# ESP32_S3.net
KiCad netlist of a schematic drawn in Altium Designer
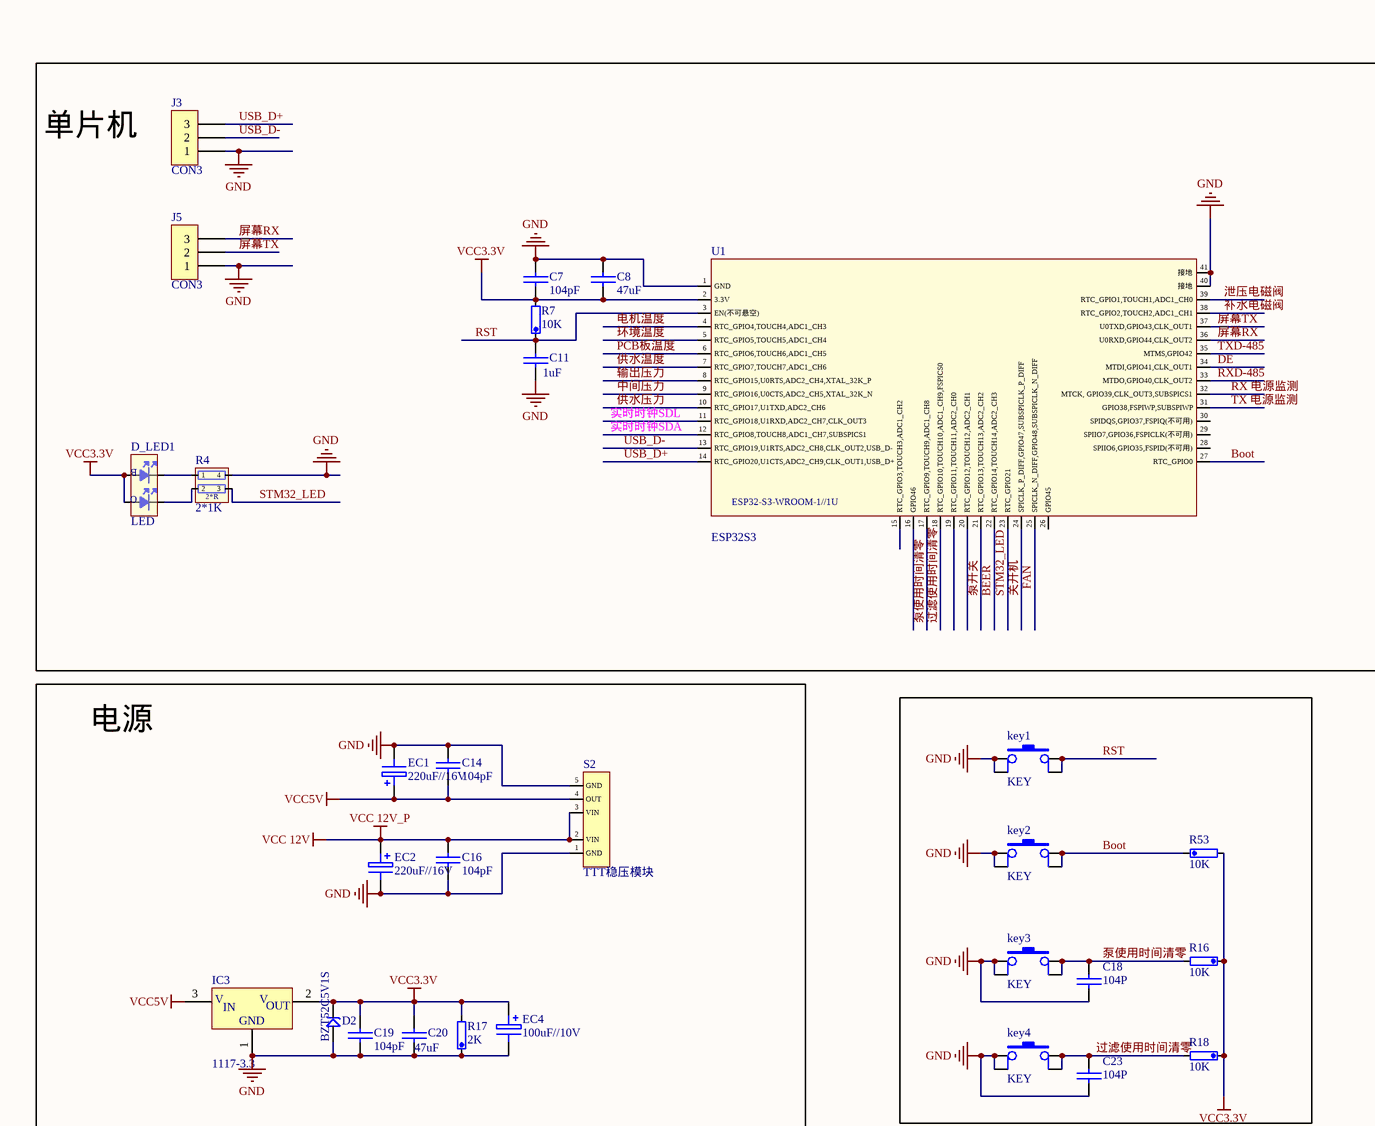
[diagram p0: 喷雾系统ESP32 S3.SchDoc, top left]
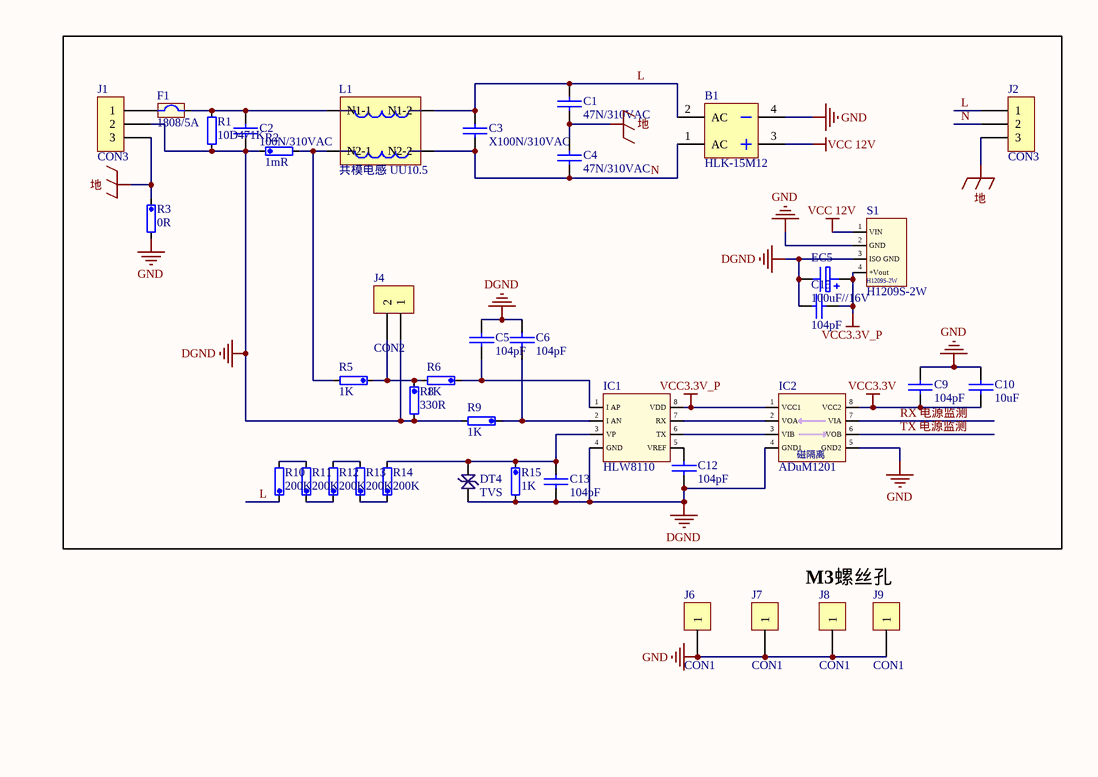
[diagram p1: 喷雾系统ESP32 S3.SchDoc, top right]
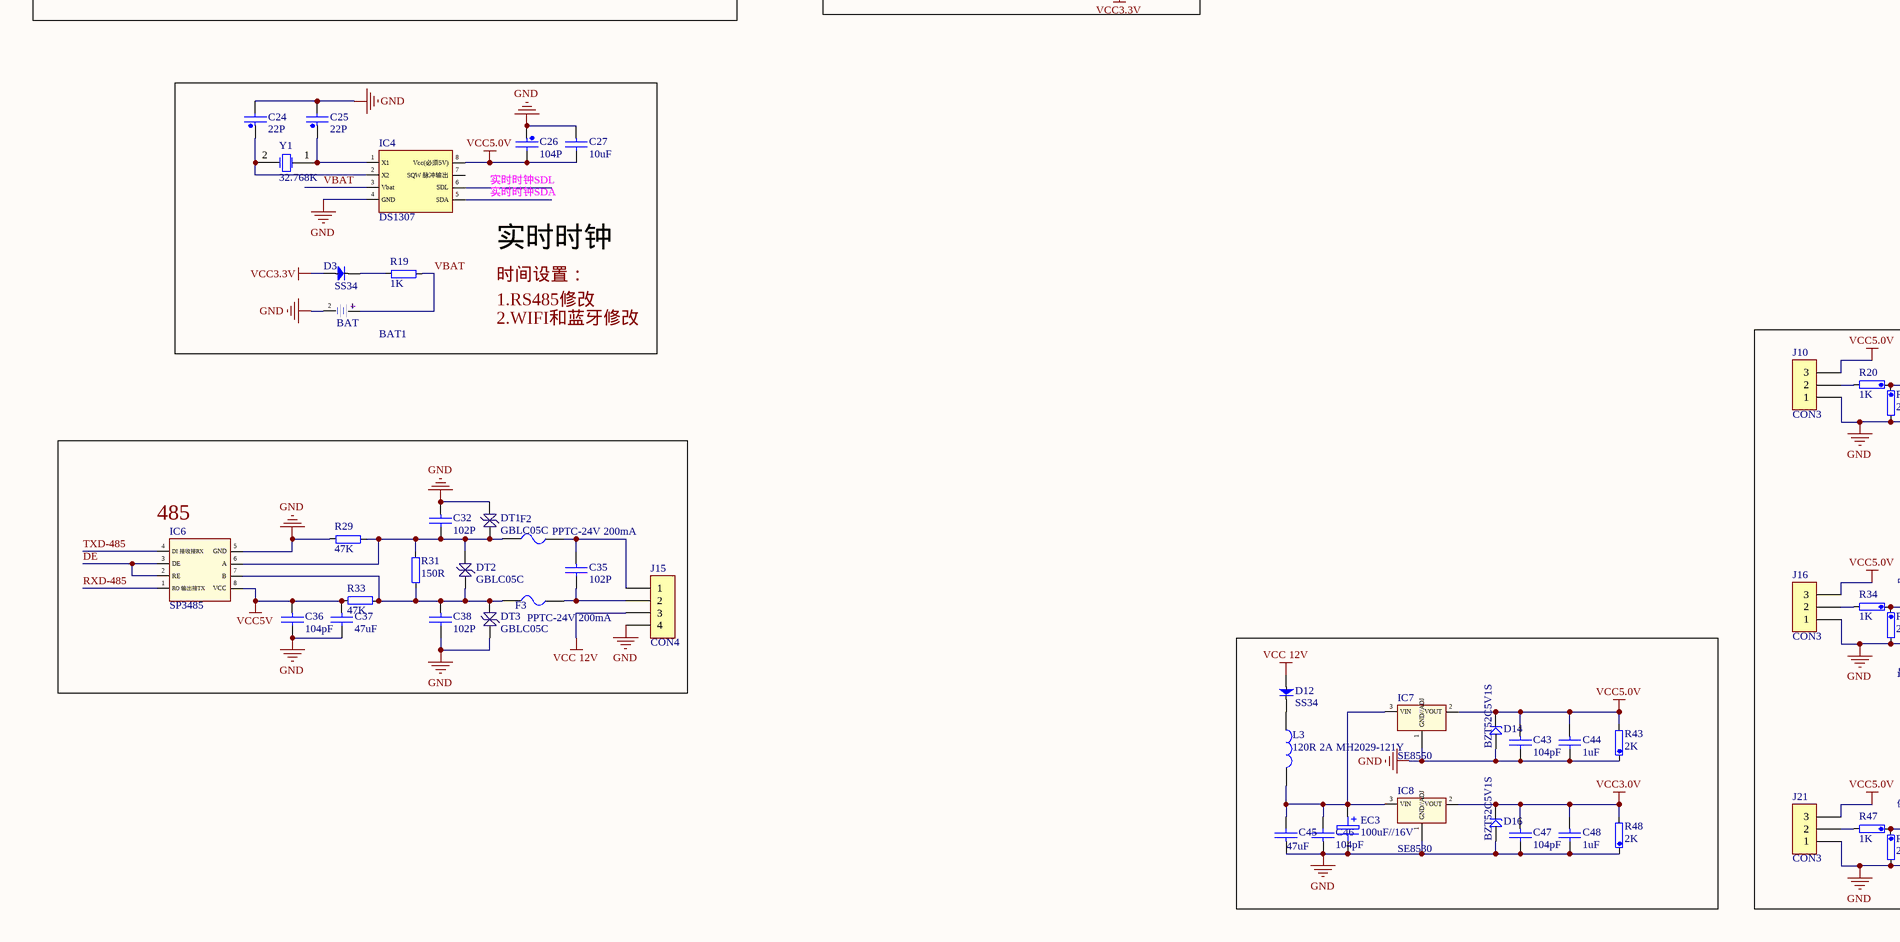
[diagram p2: 喷雾系统ESP32 S3.SchDoc, bottom left]
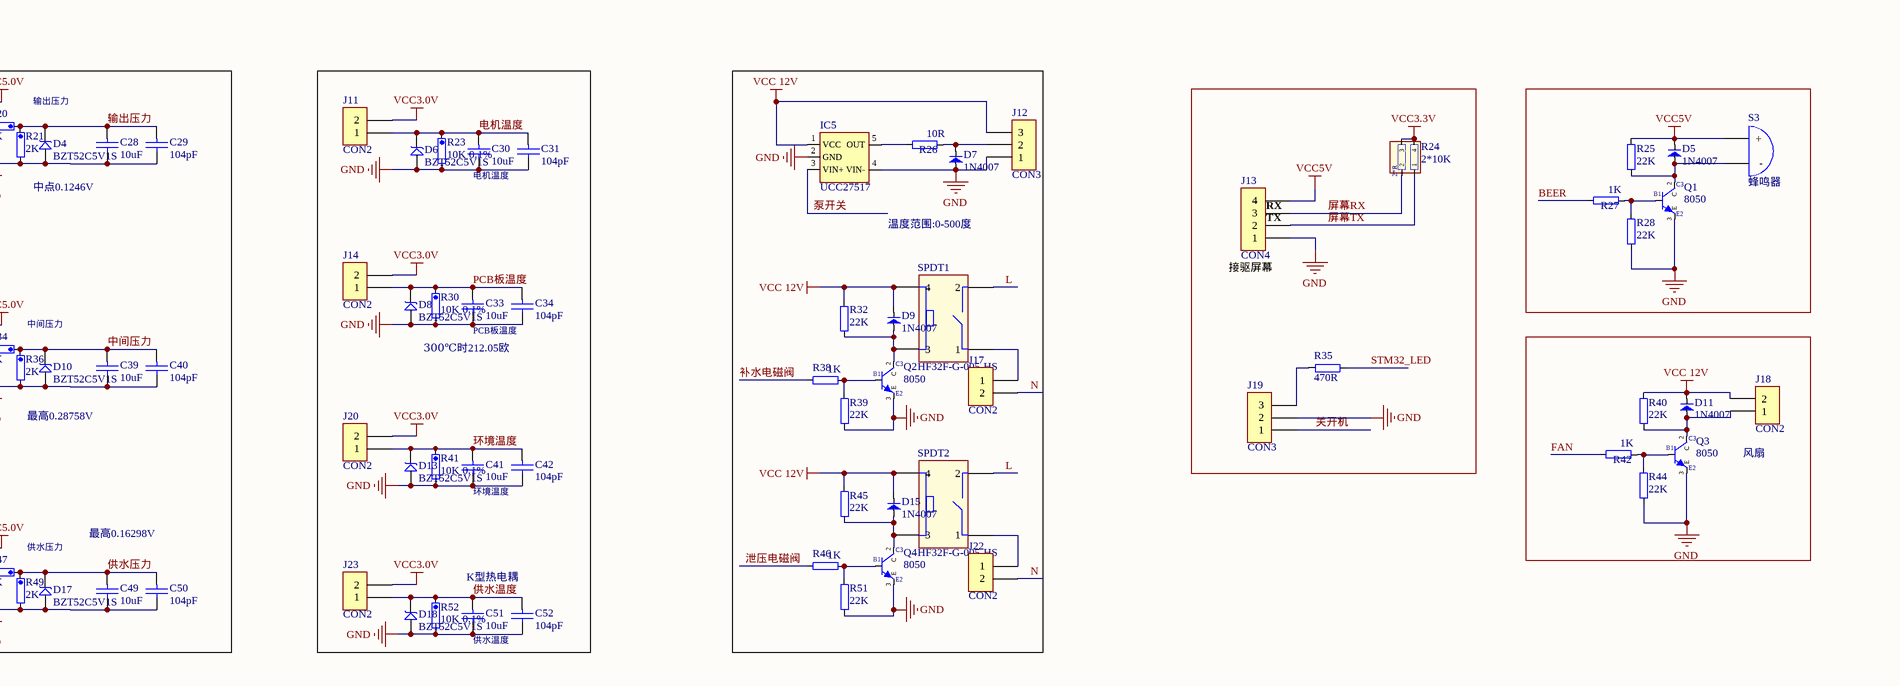
[diagram p3: 喷雾系统ESP32 S3.SchDoc, bottom right]

(export (version "E")
  (design (tool "Eeschema 10.0.6"))
  (components
    (comp (ref "B1")
      (value "HLK-15M12")
      (footprint "电源模块15W AC转DC HI-link")
      (description "HI-link")
      (libsource (lib "西洲电子元件库") (part "AC-DC模块"))
    )
    (comp (ref "BAT1")
      (value "BAT")
      (footprint "直插锂电池")
      (description "电池")
      (libsource (lib "西洲电子元件库") (part "电池 BAT"))
    )
    (comp (ref "C1") (value "47N/310VAC") (footprint "安规Y电容") (libsource (lib "功放DIY") (part "CAP")))
    (comp (ref "C2") (value "100N/310VAC") (footprint "安规X电容") (libsource (lib "功放DIY") (part "CAP")))
    (comp (ref "C3")
      (value "X100N/310VAC")
      (footprint "安规X电容")
      (description "安规电容")
      (libsource (lib "西洲电子元件库") (part "CAP"))
    )
    (comp (ref "C4") (value "47N/310VAC") (footprint "安规Y电容") (libsource (lib "功放DIY") (part "CAP")))
    (comp (ref "C5")
      (value "104pF")
      (footprint "B0805")
      (description "电容")
      (libsource (lib "西洲电子元件库") (part "CAP"))
    )
    (comp (ref "C6")
      (value "104pF")
      (footprint "B0805")
      (description "电容")
      (libsource (lib "西洲电子元件库") (part "CAP"))
    )
    (comp (ref "C7")
      (value "104pF")
      (footprint "B0805")
      (description "电容")
      (libsource (lib "西洲电子元件库") (part "CAP"))
    )
    (comp (ref "C8")
      (value "47uF")
      (footprint "B0805")
      (description "电容")
      (libsource (lib "西洲电子元件库") (part "CAP"))
    )
    (comp (ref "C9")
      (value "104pF")
      (footprint "B0805")
      (description "电容")
      (libsource (lib "西洲电子元件库") (part "CAP"))
    )
    (comp (ref "C10")
      (value "10uF")
      (footprint "B0805")
      (description "电容")
      (libsource (lib "西洲电子元件库") (part "CAP"))
    )
    (comp (ref "C11")
      (value "1uF")
      (footprint "B0805")
      (description "电容")
      (libsource (lib "西洲电子元件库") (part "CAP"))
    )
    (comp (ref "C12")
      (value "104pF")
      (footprint "B0805")
      (description "电容")
      (libsource (lib "西洲电子元件库") (part "CAP"))
    )
    (comp (ref "C13")
      (value "104pF")
      (footprint "B0805")
      (description "电容")
      (libsource (lib "西洲电子元件库") (part "CAP"))
    )
    (comp (ref "C14") (value "104pF") (footprint "B0805") (libsource (lib "功放DIY") (part "CAP")))
    (comp (ref "C15")
      (value "104pF")
      (footprint "B0805")
      (description "电容")
      (libsource (lib "西洲电子元件库") (part "CAP"))
    )
    (comp (ref "C16") (value "104pF") (footprint "B0805") (libsource (lib "功放DIY") (part "CAP")))
    (comp (ref "C18") (value "104P") (footprint "B0805") (libsource (lib "功放DIY") (part "CAP")))
    (comp (ref "C19")
      (value "104pF")
      (footprint "B0805")
      (description "电容")
      (libsource (lib "西洲电子元件库") (part "CAP"))
    )
    (comp (ref "C20")
      (value "47uF")
      (footprint "B0805")
      (description "电容")
      (libsource (lib "西洲电子元件库") (part "CAP"))
    )
    (comp (ref "C23") (value "104P") (footprint "B0805") (libsource (lib "功放DIY") (part "CAP")))
    (comp (ref "C24") (value "22P") (footprint "B0603") (libsource (lib "") (part "CAP_1")))
    (comp (ref "C25") (value "22P") (footprint "B0603") (libsource (lib "") (part "CAP_1")))
    (comp (ref "C26") (value "104P") (footprint "B0805") (libsource (lib "") (part "CAP_1")))
    (comp (ref "C27") (value "10uF") (footprint "B0805") (libsource (lib "功放DIY") (part "CAP")))
    (comp (ref "C28")
      (value "10uF")
      (footprint "B0805")
      (description "电容")
      (libsource (lib "西洲电子元件库") (part "CAP"))
    )
    (comp (ref "C29")
      (value "104pF")
      (footprint "B0805")
      (description "电容")
      (libsource (lib "西洲电子元件库") (part "CAP"))
    )
    (comp (ref "C30")
      (value "10uF")
      (footprint "B0805")
      (description "电容")
      (libsource (lib "西洲电子元件库") (part "CAP"))
    )
    (comp (ref "C31")
      (value "104pF")
      (footprint "B0805")
      (description "电容")
      (libsource (lib "西洲电子元件库") (part "CAP"))
    )
    (comp (ref "C32") (value "102P") (footprint "B0805") (libsource (lib "功放DIY") (part "CAP")))
    (comp (ref "C33")
      (value "10uF")
      (footprint "B0805")
      (description "电容")
      (libsource (lib "西洲电子元件库") (part "CAP"))
    )
    (comp (ref "C34")
      (value "104pF")
      (footprint "B0805")
      (description "电容")
      (libsource (lib "西洲电子元件库") (part "CAP"))
    )
    (comp (ref "C35") (value "102P") (footprint "B0805") (libsource (lib "功放DIY") (part "CAP")))
    (comp (ref "C36")
      (value "104pF")
      (footprint "B0805")
      (description "电容")
      (libsource (lib "西洲电子元件库") (part "CAP"))
    )
    (comp (ref "C37")
      (value "47uF")
      (footprint "B0805")
      (description "电容")
      (libsource (lib "西洲电子元件库") (part "CAP"))
    )
    (comp (ref "C38") (value "102P") (footprint "B0805") (libsource (lib "功放DIY") (part "CAP")))
    (comp (ref "C39")
      (value "10uF")
      (footprint "B0805")
      (description "电容")
      (libsource (lib "西洲电子元件库") (part "CAP"))
    )
    (comp (ref "C40")
      (value "104pF")
      (footprint "B0805")
      (description "电容")
      (libsource (lib "西洲电子元件库") (part "CAP"))
    )
    (comp (ref "C41")
      (value "10uF")
      (footprint "B0805")
      (description "电容")
      (libsource (lib "西洲电子元件库") (part "CAP"))
    )
    (comp (ref "C42")
      (value "104pF")
      (footprint "B0805")
      (description "电容")
      (libsource (lib "西洲电子元件库") (part "CAP"))
    )
    (comp (ref "C43")
      (value "104pF")
      (footprint "B0805")
      (description "电容")
      (libsource (lib "西洲电子元件库") (part "CAP"))
    )
    (comp (ref "C44")
      (value "1uF")
      (footprint "B0805")
      (description "电容")
      (libsource (lib "西洲电子元件库") (part "CAP"))
    )
    (comp (ref "C45")
      (value "47uF")
      (footprint "B0805")
      (description "电容")
      (libsource (lib "西洲电子元件库") (part "CAP"))
    )
    (comp (ref "C46")
      (value "104pF")
      (footprint "B0805")
      (description "电容")
      (libsource (lib "西洲电子元件库") (part "CAP"))
    )
    (comp (ref "C47")
      (value "104pF")
      (footprint "B0805")
      (description "电容")
      (libsource (lib "西洲电子元件库") (part "CAP"))
    )
    (comp (ref "C48")
      (value "1uF")
      (footprint "B0805")
      (description "电容")
      (libsource (lib "西洲电子元件库") (part "CAP"))
    )
    (comp (ref "C49")
      (value "10uF")
      (footprint "B0805")
      (description "电容")
      (libsource (lib "西洲电子元件库") (part "CAP"))
    )
    (comp (ref "C50")
      (value "104pF")
      (footprint "B0805")
      (description "电容")
      (libsource (lib "西洲电子元件库") (part "CAP"))
    )
    (comp (ref "C51")
      (value "10uF")
      (footprint "B0805")
      (description "电容")
      (libsource (lib "西洲电子元件库") (part "CAP"))
    )
    (comp (ref "C52")
      (value "104pF")
      (footprint "B0805")
      (description "电容")
      (libsource (lib "西洲电子元件库") (part "CAP"))
    )
    (comp (ref "D2") (value "BZT52C5V1S") (footprint "SOD-323") (libsource (lib "西洲电子元件库") (part "单向稳压二极管")))
    (comp (ref "D3") (value "SS34") (footprint "SOD-323") (libsource (lib "") (part "DIODE_1")))
    (comp (ref "D4") (value "BZT52C5V1S") (footprint "SOD-323") (libsource (lib "西洲电子元件库") (part "单向稳压二极管")))
    (comp (ref "D5") (value "1N4007") (footprint "SOD-323") (libsource (lib "西洲电子元件库") (part "DIODE")))
    (comp (ref "D6") (value "BZT52C5V1S") (footprint "SOD-323") (libsource (lib "西洲电子元件库") (part "单向稳压二极管")))
    (comp (ref "D7") (value "1N4007") (footprint "SOD-323") (libsource (lib "西洲电子元件库") (part "DIODE")))
    (comp (ref "D8") (value "BZT52C5V1S") (footprint "SOD-323") (libsource (lib "西洲电子元件库") (part "单向稳压二极管")))
    (comp (ref "D9") (value "1N4007") (footprint "SOD-323") (libsource (lib "西洲电子元件库") (part "DIODE")))
    (comp (ref "D10") (value "BZT52C5V1S") (footprint "SOD-323") (libsource (lib "西洲电子元件库") (part "单向稳压二极管")))
    (comp (ref "D11") (value "1N4007") (footprint "SOD-323") (libsource (lib "西洲电子元件库") (part "DIODE")))
    (comp (ref "D12") (value "SS34") (footprint "SOD-323") (libsource (lib "") (part "DIODE_1")))
    (comp (ref "D13") (value "BZT52C5V1S") (footprint "SOD-323") (libsource (lib "西洲电子元件库") (part "单向稳压二极管")))
    (comp (ref "D14") (value "BZT52C5V1S") (footprint "SOD-323") (libsource (lib "西洲电子元件库") (part "单向稳压二极管")))
    (comp (ref "D15") (value "1N4007") (footprint "SOD-323") (libsource (lib "西洲电子元件库") (part "DIODE")))
    (comp (ref "D16") (value "BZT52C5V1S") (footprint "SOD-323") (libsource (lib "西洲电子元件库") (part "单向稳压二极管")))
    (comp (ref "D17") (value "BZT52C5V1S") (footprint "SOD-323") (libsource (lib "西洲电子元件库") (part "单向稳压二极管")))
    (comp (ref "D18") (value "BZT52C5V1S") (footprint "SOD-323") (libsource (lib "西洲电子元件库") (part "单向稳压二极管")))
    (comp (ref "DT1") (value "GBLC05C") (footprint "SOD-323-12") (libsource (lib "西洲电子元件库") (part "TVS")))
    (comp (ref "DT2") (value "GBLC05C") (footprint "SOD-323-12") (libsource (lib "西洲电子元件库") (part "TVS")))
    (comp (ref "DT3") (value "GBLC05C") (footprint "SOD-323-12") (libsource (lib "西洲电子元件库") (part "TVS")))
    (comp (ref "DT4") (value "TVS") (footprint "SOD-323") (libsource (lib "") (part "TVS_1")))
    (comp (ref "D_LED1")
      (value "LED")
      (footprint "双色LED 1615")
      (description "双色LED 橙蓝")
      (libsource (lib "西洲电子元件库") (part "双色LED 橙蓝"))
    )
    (comp (ref "EC1") (value "220uF//16V") (footprint "贴片电容6.3*5.4") (libsource (lib "功放DIY") (part "EC")))
    (comp (ref "EC2") (value "220uF//16V") (footprint "贴片电容6.3*5.4") (libsource (lib "功放DIY") (part "EC")))
    (comp (ref "EC3") (value "100uF//16V") (footprint "C型 电容") (libsource (lib "功放DIY") (part "EC")))
    (comp (ref "EC4") (value "100uF//10V") (footprint "C型 电容") (libsource (lib "功放DIY") (part "EC")))
    (comp (ref "EC5") (value "100uF//16V") (footprint "C型 电容") (libsource (lib "功放DIY") (part "EC")))
    (comp (ref "F1") (value "1808/5A") (footprint "1808贴片保险") (libsource (lib "功放DIY") (part "保险")))
    (comp (ref "F2")
      (value "PPTC-24V 200mA")
      (footprint "FU 0805")
      (description "贴片保险丝")
      (fields (field (name "版权归属") "源创客"))
      (libsource (lib "保险丝-晶振") (part "FU"))
    )
    (comp (ref "F3")
      (value "PPTC-24V 200mA")
      (footprint "FU 0805")
      (description "贴片保险丝")
      (fields (field (name "版权归属") "源创客"))
      (libsource (lib "保险丝-晶振") (part "FU"))
    )
    (comp (ref "IC1")
      (value "HLW8110")
      (footprint "SOP8")
      (description "电能计量")
      (libsource (lib "西洲电子元件库") (part "HLW8110"))
    )
    (comp (ref "IC2")
      (value "ADuM1201")
      (footprint "SOP8")
      (description "磁隔离 ADuM1201")
      (libsource (lib "西洲电子元件库") (part "磁隔离"))
    )
    (comp (ref "IC3") (value "1117-3.3") (footprint "SOT-223") (libsource (lib "西洲电子元件库") (part "1117")))
    (comp (ref "IC4") (value "DS1307") (footprint "SOP8") (libsource (lib "西洲电子元件库") (part "DS1307")))
    (comp (ref "IC5")
      (value "UCC27517")
      (footprint "SOT23-5")
      (description "场管驱动")
      (libsource (lib "西洲电子元件库") (part "场管驱动 UCC27517"))
    )
    (comp (ref "IC6")
      (value "SP3485")
      (footprint "SOP8")
      (description "RS485 收发")
      (libsource (lib "西洲电子元件库") (part "SP3485"))
    )
    (comp (ref "IC7")
      (value "SE8550")
      (footprint "SOT_89")
      (description "稳压LOD+")
      (libsource (lib "西洲电子元件库") (part "稳压LOD+ 2脚输出"))
    )
    (comp (ref "IC8")
      (value "SE8530")
      (footprint "SOT23_231")
      (description "稳压LOD+")
      (libsource (lib "西洲电子元件库") (part "稳压LOD+ 2脚输出"))
    )
    (comp (ref "J1")
      (value "CON3")
      (footprint "CON3_5.08 弯")
      (description "Connector")
      (libsource (lib "") (part "CON3_2"))
    )
    (comp (ref "J2")
      (value "CON3")
      (footprint "CON3_5.08 弯")
      (description "Connector")
      (libsource (lib "") (part "CON3_3"))
    )
    (comp (ref "J3")
      (value "CON3")
      (footprint "SIP3_2.0")
      (description "Connector")
      (libsource (lib "西洲电子元件库") (part "CON3"))
    )
    (comp (ref "J4")
      (value "CON2")
      (footprint "XH2.54-2P 弯")
      (description "Connector")
      (libsource (lib "") (part "CON2_1"))
    )
    (comp (ref "J5")
      (value "CON3")
      (footprint "SIP3_2.0")
      (description "Connector")
      (libsource (lib "西洲电子元件库") (part "CON3"))
    )
    (comp (ref "J6")
      (value "CON1")
      (footprint "螺丝孔")
      (description "Connector")
      (libsource (lib "功放DIY") (part "CON1"))
    )
    (comp (ref "J7")
      (value "CON1")
      (footprint "螺丝孔")
      (description "Connector")
      (libsource (lib "功放DIY") (part "CON1"))
    )
    (comp (ref "J8")
      (value "CON1")
      (footprint "螺丝孔")
      (description "Connector")
      (libsource (lib "功放DIY") (part "CON1"))
    )
    (comp (ref "J9")
      (value "CON1")
      (footprint "螺丝孔")
      (description "Connector")
      (libsource (lib "功放DIY") (part "CON1"))
    )
    (comp (ref "J10")
      (value "CON3")
      (footprint "XHB2.54-3")
      (description "Connector")
      (libsource (lib "西洲电子元件库") (part "CON3"))
    )
    (comp (ref "J11")
      (value "CON2")
      (footprint "PH2.0_2P_直针")
      (description "Connector")
      (libsource (lib "") (part "CON2_3"))
    )
    (comp (ref "J12")
      (value "CON3")
      (footprint "XHB2.54-3")
      (description "Connector")
      (libsource (lib "") (part "CON3_1"))
    )
    (comp (ref "J13")
      (value "CON4")
      (footprint "XHB2.54_4")
      (description "Connector")
      (libsource (lib "") (part "CON4_1"))
    )
    (comp (ref "J14")
      (value "CON2")
      (footprint "PH2.0_2P_直针")
      (description "Connector")
      (libsource (lib "") (part "CON2_3"))
    )
    (comp (ref "J15")
      (value "CON4")
      (footprint "XHB2.54_4")
      (description "Connector")
      (libsource (lib "西洲电子元件库") (part "CON4"))
    )
    (comp (ref "J16")
      (value "CON3")
      (footprint "XHB2.54-3")
      (description "Connector")
      (libsource (lib "西洲电子元件库") (part "CON3"))
    )
    (comp (ref "J17")
      (value "CON2")
      (footprint "CON2-5.08 弯")
      (description "Connector")
      (libsource (lib "") (part "CON2_2"))
    )
    (comp (ref "J18")
      (value "CON2")
      (footprint "XHB2.54-2")
      (description "Connector")
      (libsource (lib "西洲电子元件库") (part "CON2"))
    )
    (comp (ref "J19")
      (value "CON3")
      (footprint "PH2.0_3P_直针")
      (description "Connector")
      (libsource (lib "西洲电子元件库") (part "CON3"))
    )
    (comp (ref "J20")
      (value "CON2")
      (footprint "PH2.0_2P_直针")
      (description "Connector")
      (libsource (lib "") (part "CON2_3"))
    )
    (comp (ref "J21")
      (value "CON3")
      (footprint "XHB2.54-3")
      (description "Connector")
      (libsource (lib "西洲电子元件库") (part "CON3"))
    )
    (comp (ref "J22")
      (value "CON2")
      (footprint "CON2-5.08 弯")
      (description "Connector")
      (libsource (lib "") (part "CON2_2"))
    )
    (comp (ref "J23")
      (value "CON2")
      (footprint "PH2.0_2P_直针")
      (description "Connector")
      (libsource (lib "") (part "CON2_3"))
    )
    (comp (ref "key1") (value "KEY") (footprint "3*4*2.5按键") (libsource (lib "功放DIY") (part "KEY")))
    (comp (ref "key2") (value "KEY") (footprint "3*4*2.5按键") (libsource (lib "功放DIY") (part "KEY")))
    (comp (ref "key3") (value "KEY") (footprint "3*4*2.5按键") (libsource (lib "功放DIY") (part "KEY")))
    (comp (ref "key4") (value "KEY") (footprint "3*4*2.5按键") (libsource (lib "功放DIY") (part "KEY")))
    (comp (ref "L1")
      (value "共模电感 UU10.5")
      (footprint "UU10 共模电感")
      (libsource (lib "西洲电子元件库") (part "共模电感 UU10.5"))
    )
    (comp (ref "L3")
      (value "120R 2A MH2029-121Y")
      (footprint "B0805")
      (libsource (lib "西洲电子元件库") (part "INDUCTOR"))
    )
    (comp (ref "Q1")
      (value "8050")
      (footprint "SOT231")
      (description "NPN Transistor")
      (libsource (lib "西洲电子元件库") (part "NPN"))
    )
    (comp (ref "Q2")
      (value "8050")
      (footprint "SOT231")
      (description "NPN Transistor")
      (libsource (lib "西洲电子元件库") (part "NPN"))
    )
    (comp (ref "Q3")
      (value "8050")
      (footprint "SOT231")
      (description "NPN Transistor")
      (libsource (lib "西洲电子元件库") (part "NPN"))
    )
    (comp (ref "Q4")
      (value "8050")
      (footprint "SOT231")
      (description "NPN Transistor")
      (libsource (lib "西洲电子元件库") (part "NPN"))
    )
    (comp (ref "R1") (value "10D471K") (footprint "10D471K") (libsource (lib "功放DIY") (part "RES")))
    (comp (ref "R2") (value "1mR") (footprint "B2410") (libsource (lib "西洲电子元件库") (part "RES")))
    (comp (ref "R3") (value "0R") (footprint "B0805") (libsource (lib "西洲电子元件库") (part "RES")))
    (comp (ref "R4")
      (value "2*1K")
      (footprint "B0402-2")
      (description "排阻2P")
      (libsource (lib "西洲电子元件库") (part "排阻2P"))
    )
    (comp (ref "R5") (value "1K") (footprint "B0603") (libsource (lib "西洲电子元件库") (part "RES")))
    (comp (ref "R6") (value "1K") (footprint "B0603") (libsource (lib "西洲电子元件库") (part "RES")))
    (comp (ref "R7") (value "10K") (footprint "B0603") (libsource (lib "西洲电子元件库") (part "RES")))
    (comp (ref "R8") (value "330R") (footprint "B0805") (libsource (lib "西洲电子元件库") (part "RES")))
    (comp (ref "R9") (value "1K") (footprint "B0603") (libsource (lib "西洲电子元件库") (part "RES")))
    (comp (ref "R10") (value "200K") (footprint "B0603") (libsource (lib "西洲电子元件库") (part "RES")))
    (comp (ref "R11") (value "200K") (footprint "B0603") (libsource (lib "西洲电子元件库") (part "RES")))
    (comp (ref "R12") (value "200K") (footprint "B0603") (libsource (lib "西洲电子元件库") (part "RES")))
    (comp (ref "R13") (value "200K") (footprint "B0603") (libsource (lib "西洲电子元件库") (part "RES")))
    (comp (ref "R14") (value "200K") (footprint "B0603") (libsource (lib "西洲电子元件库") (part "RES")))
    (comp (ref "R15") (value "1K") (footprint "B0805") (libsource (lib "西洲电子元件库") (part "RES")))
    (comp (ref "R16") (value "10K") (footprint "B0603") (libsource (lib "西洲电子元件库") (part "RES")))
    (comp (ref "R17") (value "2K") (footprint "B0603") (libsource (lib "西洲电子元件库") (part "RES")))
    (comp (ref "R18") (value "10K") (footprint "B0603") (libsource (lib "西洲电子元件库") (part "RES")))
    (comp (ref "R19") (value "1K") (footprint "B0603") (libsource (lib "功放DIY") (part "RES")))
    (comp (ref "R20") (value "1K") (footprint "B0603") (libsource (lib "西洲电子元件库") (part "RES")))
    (comp (ref "R21") (value "2K") (footprint "B0603") (libsource (lib "西洲电子元件库") (part "RES")))
    (comp (ref "R23") (value "10K 0.1%") (footprint "B0603") (libsource (lib "西洲电子元件库") (part "RES")))
    (comp (ref "R24")
      (value "2*10K")
      (footprint "B0402-2")
      (description "排阻2P")
      (libsource (lib "西洲电子元件库") (part "排阻2P"))
    )
    (comp (ref "R25") (value "22K") (footprint "B0603") (libsource (lib "功放DIY") (part "RES")))
    (comp (ref "R26") (value "10R") (footprint "B0603") (libsource (lib "功放DIY") (part "RES")))
    (comp (ref "R27") (value "1K") (footprint "B0603") (libsource (lib "功放DIY") (part "RES")))
    (comp (ref "R28") (value "22K") (footprint "B0603") (libsource (lib "功放DIY") (part "RES")))
    (comp (ref "R29") (value "47K") (footprint "B0603") (libsource (lib "功放DIY") (part "RES")))
    (comp (ref "R30") (value "10K 0.1%") (footprint "B0603") (libsource (lib "西洲电子元件库") (part "RES")))
    (comp (ref "R31") (value "150R") (footprint "B0603") (libsource (lib "功放DIY") (part "RES")))
    (comp (ref "R32") (value "22K") (footprint "B0603") (libsource (lib "功放DIY") (part "RES")))
    (comp (ref "R33") (value "47K") (footprint "B0603") (libsource (lib "功放DIY") (part "RES")))
    (comp (ref "R34") (value "1K") (footprint "B0603") (libsource (lib "西洲电子元件库") (part "RES")))
    (comp (ref "R35") (value "470R") (footprint "B0603") (libsource (lib "功放DIY") (part "RES")))
    (comp (ref "R36") (value "2K") (footprint "B0603") (libsource (lib "西洲电子元件库") (part "RES")))
    (comp (ref "R38") (value "1K") (footprint "B0603") (libsource (lib "功放DIY") (part "RES")))
    (comp (ref "R39") (value "22K") (footprint "B0603") (libsource (lib "功放DIY") (part "RES")))
    (comp (ref "R40") (value "22K") (footprint "B0603") (libsource (lib "功放DIY") (part "RES")))
    (comp (ref "R41") (value "10K 0.1%") (footprint "B0603") (libsource (lib "西洲电子元件库") (part "RES")))
    (comp (ref "R42") (value "1K") (footprint "B0603") (libsource (lib "功放DIY") (part "RES")))
    (comp (ref "R43") (value "2K") (footprint "B0603") (libsource (lib "西洲电子元件库") (part "RES")))
    (comp (ref "R44") (value "22K") (footprint "B0603") (libsource (lib "功放DIY") (part "RES")))
    (comp (ref "R45") (value "22K") (footprint "B0603") (libsource (lib "功放DIY") (part "RES")))
    (comp (ref "R46") (value "1K") (footprint "B0603") (libsource (lib "功放DIY") (part "RES")))
    (comp (ref "R47") (value "1K") (footprint "B0603") (libsource (lib "西洲电子元件库") (part "RES")))
    (comp (ref "R48") (value "2K") (footprint "B0603") (libsource (lib "西洲电子元件库") (part "RES")))
    (comp (ref "R49") (value "2K") (footprint "B0603") (libsource (lib "西洲电子元件库") (part "RES")))
    (comp (ref "R51") (value "22K") (footprint "B0603") (libsource (lib "功放DIY") (part "RES")))
    (comp (ref "R52") (value "10K 0.1%") (footprint "B0603") (libsource (lib "西洲电子元件库") (part "RES")))
    (comp (ref "R53") (value "10K") (footprint "B0603") (libsource (lib "西洲电子元件库") (part "RES")))
    (comp (ref "S1")
      (value "H1209S-2W")
      (footprint "隔离电源 H1209S")
      (libsource (lib "西洲电子元件库") (part "隔离电源 H1209S-2W"))
    )
    (comp (ref "S2") (value "TTT稳压模块") (footprint "TTT稳压模块") (libsource (lib "西洲电子元件库") (part "TTT稳压模块")))
    (comp (ref "S3") (value "蜂鸣器") (footprint "12065蜂鸣器7.62") (libsource (lib "功放DIY") (part "蜂鸣器")))
    (comp (ref "SPDT1")
      (value "HF32F-G-005-HS")
      (footprint "HF32FV")
      (libsource (lib "西洲电子元件库") (part "继电器Relay"))
    )
    (comp (ref "SPDT2")
      (value "HF32F-G-005-HS")
      (footprint "HF32FV")
      (libsource (lib "西洲电子元件库") (part "继电器Relay"))
    )
    (comp (ref "U1")
      (value "ESP32S3")
      (footprint "ESP32-S3-WROOM-1U")
      (libsource (lib "西洲电子元件库") (part "ESP32S3"))
    )
    (comp (ref "Y1")
      (value "32.768K")
      (footprint "晶振 FC135")
      (description "Crystal Oscillator")
      (fields (field (name "PUBLISHER") "Altium Limited"))
      (libsource (lib "Explorer STM32F407封装库") (part "XTAL"))
    )
  )
  (nets
    (net (code "1") (name "/BEER") (class "Default")
      (node (ref "R27") (pin "2") (pinfunction "2_2") (pintype "passive"))
      (node (ref "U1") (pin "22") (pinfunction "RTC_GPIO14,TOUCH14,ADC2_CH3_22") (pintype "passive"))
    )
    (net (code "2") (name "/Boot") (class "Default")
      (node (ref "R53") (pin "1") (pinfunction "1_1") (pintype "passive"))
      (node (ref "U1") (pin "27") (pinfunction "RTC_GPIO0_27") (pintype "passive"))
      (node (ref "key2") (pin "3") (pinfunction "3_3") (pintype "passive"))
      (node (ref "key2") (pin "4") (pinfunction "4_4") (pintype "passive"))
    )
    (net (code "3") (name "/DE") (class "Default")
      (node (ref "IC6") (pin "2") (pinfunction "RE_2") (pintype "passive"))
      (node (ref "IC6") (pin "3") (pinfunction "DE_3") (pintype "passive"))
      (node (ref "U1") (pin "34") (pinfunction "MTDI,GPIO41,CLK_OUT1_34") (pintype "passive"))
    )
    (net (code "4") (name "/FAN") (class "Default")
      (node (ref "R42") (pin "2") (pinfunction "2_2") (pintype "passive"))
      (node (ref "U1") (pin "25") (pinfunction "SPICLK_N_DIFF,GPIO48,SUBSPICLK_N_DIFF_25") (pintype "passive"))
    )
    (net (code "5") (name "/L") (class "Default")
      (node (ref "B1") (pin "2") (pinfunction "AC_2") (pintype "passive"))
      (node (ref "C1") (pin "2") (pinfunction "2_2") (pintype "passive"))
      (node (ref "C3") (pin "1") (pinfunction "1_1") (pintype "passive"))
      (node (ref "J2") (pin "1") (pinfunction "1_1") (pintype "passive"))
      (node (ref "L1") (pin "2") (pinfunction "N1-2_2") (pintype "passive"))
      (node (ref "R10") (pin "1") (pinfunction "1_1") (pintype "passive"))
      (node (ref "SPDT1") (pin "2") (pinfunction "2_2") (pintype "passive"))
      (node (ref "SPDT2") (pin "2") (pinfunction "2_2") (pintype "passive"))
    )
    (net (code "6") (name "/N") (class "Default")
      (node (ref "B1") (pin "1") (pinfunction "AC_1") (pintype "passive"))
      (node (ref "C3") (pin "2") (pinfunction "2_2") (pintype "passive"))
      (node (ref "C4") (pin "1") (pinfunction "1_1") (pintype "passive"))
      (node (ref "J17") (pin "2") (pinfunction "2_2") (pintype "passive"))
      (node (ref "J2") (pin "2") (pinfunction "2_2") (pintype "passive"))
      (node (ref "J22") (pin "2") (pinfunction "2_2") (pintype "passive"))
      (node (ref "L1") (pin "4") (pinfunction "N2-2_4") (pintype "passive"))
    )
    (net (code "7") (name "/PCB板温度") (class "Default")
      (node (ref "C33") (pin "1") (pinfunction "1_1") (pintype "passive"))
      (node (ref "C34") (pin "1") (pinfunction "1_1") (pintype "passive"))
      (node (ref "D8") (pin "K") (pintype "passive"))
      (node (ref "J14") (pin "1") (pinfunction "1_1") (pintype "passive"))
      (node (ref "R30") (pin "1") (pinfunction "1_1") (pintype "passive"))
      (node (ref "U1") (pin "6") (pinfunction "RTC_GPIO6,TOUCH6,ADC1_CH5_6") (pintype "passive"))
    )
    (net (code "8") (name "/RST") (class "Default")
      (node (ref "C11") (pin "1") (pinfunction "1_1") (pintype "passive"))
      (node (ref "R7") (pin "1") (pinfunction "1_1") (pintype "passive"))
      (node (ref "U1") (pin "3") (pinfunction "EN(不可悬空)_3") (pintype "passive"))
      (node (ref "key1") (pin "3") (pinfunction "3_3") (pintype "passive"))
      (node (ref "key1") (pin "4") (pinfunction "4_4") (pintype "passive"))
    )
    (net (code "9") (name "/RX 电源监测") (class "Default")
      (node (ref "IC2") (pin "7") (pinfunction "VIA_7") (pintype "passive"))
      (node (ref "U1") (pin "32") (pinfunction "MTCK,_GPIO39,CLK_OUT3,SUBSPICS1_32") (pintype "passive"))
    )
    (net (code "10") (name "/RXD-485") (class "Default")
      (node (ref "IC6") (pin "1") (pinfunction "RO_输出接TX_1") (pintype "passive"))
      (node (ref "U1") (pin "33") (pinfunction "MTDO,GPIO40,CLK_OUT2_33") (pintype "passive"))
    )
    (net (code "11") (name "/STM32_LED") (class "Default")
      (node (ref "R35") (pin "2") (pinfunction "2_2") (pintype "passive"))
      (node (ref "R4") (pin "3") (pinfunction "3_3") (pintype "passive"))
      (node (ref "U1") (pin "23") (pinfunction "RTC_GPIO21_23") (pintype "passive"))
    )
    (net (code "12") (name "/TX 电源监测") (class "Default")
      (node (ref "IC2") (pin "6") (pinfunction "VOB_6") (pintype "passive"))
      (node (ref "U1") (pin "31") (pinfunction "GPIO38,FSPIWP,SUBSPIWP_31") (pintype "passive"))
    )
    (net (code "13") (name "/TXD-485") (class "Default")
      (node (ref "IC6") (pin "4") (pinfunction "DI_接收接RX_4") (pintype "passive"))
      (node (ref "U1") (pin "35") (pinfunction "MTMS,GPIO42_35") (pintype "passive"))
    )
    (net (code "14") (name "/USB_D+") (class "Default")
      (node (ref "J3") (pin "3") (pinfunction "3_3") (pintype "passive"))
      (node (ref "U1") (pin "14") (pinfunction "RTC_GPIO20,U1CTS,ADC2_CH9,CLK_OUT1,USB_D+_14") (pintype "passive"))
    )
    (net (code "15") (name "/USB_D-") (class "Default")
      (node (ref "J3") (pin "2") (pinfunction "2_2") (pintype "passive"))
      (node (ref "U1") (pin "13") (pinfunction "RTC_GPIO19,U1RTS,ADC2_CH8,CLK_OUT2,USB_D-_13") (pintype "passive"))
    )
    (net (code "16") (name "/VBAT") (class "Default")
      (node (ref "BAT1") (pin "1") (pinfunction "+_1") (pintype "passive"))
      (node (ref "IC4") (pin "3") (pinfunction "Vbat_3") (pintype "passive"))
      (node (ref "R19") (pin "2") (pinfunction "2_2") (pintype "passive"))
    )
    (net (code "17") (name "/中间压力") (class "Default")
      (node (ref "C39") (pin "1") (pinfunction "1_1") (pintype "passive"))
      (node (ref "C40") (pin "1") (pinfunction "1_1") (pintype "passive"))
      (node (ref "D10") (pin "K") (pintype "passive"))
      (node (ref "R34") (pin "1") (pinfunction "1_1") (pintype "passive"))
      (node (ref "R36") (pin "1") (pinfunction "1_1") (pintype "passive"))
      (node (ref "U1") (pin "9") (pinfunction "RTC_GPIO16,U0CTS,ADC2_CH5,XTAL_32K_N_9") (pintype "passive"))
    )
    (net (code "18") (name "/供水压力") (class "Default")
      (node (ref "C49") (pin "1") (pinfunction "1_1") (pintype "passive"))
      (node (ref "C50") (pin "1") (pinfunction "1_1") (pintype "passive"))
      (node (ref "D17") (pin "K") (pintype "passive"))
      (node (ref "R47") (pin "1") (pinfunction "1_1") (pintype "passive"))
      (node (ref "R49") (pin "1") (pinfunction "1_1") (pintype "passive"))
      (node (ref "U1") (pin "10") (pinfunction "RTC_GPIO17,U1TXD,ADC2_CH6_10") (pintype "passive"))
    )
    (net (code "19") (name "/供水温度") (class "Default")
      (node (ref "C51") (pin "1") (pinfunction "1_1") (pintype "passive"))
      (node (ref "C52") (pin "1") (pinfunction "1_1") (pintype "passive"))
      (node (ref "D18") (pin "K") (pintype "passive"))
      (node (ref "J23") (pin "1") (pinfunction "1_1") (pintype "passive"))
      (node (ref "R52") (pin "1") (pinfunction "1_1") (pintype "passive"))
      (node (ref "U1") (pin "7") (pinfunction "RTC_GPIO7,TOUCH7,ADC1_CH6_7") (pintype "passive"))
    )
    (net (code "20") (name "/关开机") (class "Default")
      (node (ref "J19") (pin "1") (pinfunction "1_1") (pintype "passive"))
      (node (ref "U1") (pin "24") (pinfunction "SPICLK_P_DIFF,GPIO47,SUBSPICLK_P_DIFF_24") (pintype "passive"))
    )
    (net (code "21") (name "/实时时钟SDA") (class "Default")
      (node (ref "IC4") (pin "5") (pinfunction "SDA_5") (pintype "passive"))
      (node (ref "U1") (pin "12") (pinfunction "RTC_GPIO8,TOUCH8,ADC1_CH7,SUBSPICS1_12") (pintype "passive"))
    )
    (net (code "22") (name "/实时时钟SDL") (class "Default")
      (node (ref "IC4") (pin "6") (pinfunction "SDL_6") (pintype "passive"))
      (node (ref "U1") (pin "11") (pinfunction "RTC_GPIO18,U1RXD,ADC2_CH7,CLK_OUT3_11") (pintype "passive"))
    )
    (net (code "23") (name "/屏幕RX") (class "Default")
      (node (ref "J13") (pin "3") (pinfunction "3_3") (pintype "passive"))
      (node (ref "J5") (pin "3") (pinfunction "3_3") (pintype "passive"))
      (node (ref "R24") (pin "2") (pinfunction "2_2") (pintype "passive"))
      (node (ref "U1") (pin "36") (pinfunction "U0RXD,GPIO44,CLK_OUT2_36") (pintype "passive"))
    )
    (net (code "24") (name "/屏幕TX") (class "Default")
      (node (ref "J13") (pin "2") (pinfunction "2_2") (pintype "passive"))
      (node (ref "J5") (pin "2") (pinfunction "2_2") (pintype "passive"))
      (node (ref "R24") (pin "1") (pinfunction "1_1") (pintype "passive"))
      (node (ref "U1") (pin "37") (pinfunction "U0TXD,GPIO43,CLK_OUT1_37") (pintype "passive"))
    )
    (net (code "25") (name "/泄压电磁阀") (class "Default")
      (node (ref "R46") (pin "2") (pinfunction "2_2") (pintype "passive"))
      (node (ref "U1") (pin "39") (pinfunction "RTC_GPIO1,TOUCH1,ADC1_CH0_39") (pintype "passive"))
    )
    (net (code "26") (name "/泵使用时间清零") (class "Default")
      (node (ref "C18") (pin "1") (pinfunction "1_1") (pintype "passive"))
      (node (ref "R16") (pin "2") (pinfunction "2_2") (pintype "passive"))
      (node (ref "U1") (pin "17") (pinfunction "RTC_GPIO9,TOUCH9,ADC1_CH8_17") (pintype "passive"))
      (node (ref "key3") (pin "3") (pinfunction "3_3") (pintype "passive"))
      (node (ref "key3") (pin "4") (pinfunction "4_4") (pintype "passive"))
    )
    (net (code "27") (name "/泵开关") (class "Default")
      (node (ref "IC5") (pin "3") (pinfunction "VIN+_3") (pintype "passive"))
      (node (ref "U1") (pin "21") (pinfunction "RTC_GPIO13,TOUCH13,ADC2_CH2_21") (pintype "passive"))
    )
    (net (code "28") (name "/环境温度") (class "Default")
      (node (ref "C41") (pin "1") (pinfunction "1_1") (pintype "passive"))
      (node (ref "C42") (pin "1") (pinfunction "1_1") (pintype "passive"))
      (node (ref "D13") (pin "K") (pintype "passive"))
      (node (ref "J20") (pin "1") (pinfunction "1_1") (pintype "passive"))
      (node (ref "R41") (pin "1") (pinfunction "1_1") (pintype "passive"))
      (node (ref "U1") (pin "5") (pinfunction "RTC_GPIO5,TOUCH5,ADC1_CH4_5") (pintype "passive"))
    )
    (net (code "29") (name "/电机温度") (class "Default")
      (node (ref "C30") (pin "1") (pinfunction "1_1") (pintype "passive"))
      (node (ref "C31") (pin "1") (pinfunction "1_1") (pintype "passive"))
      (node (ref "D6") (pin "K") (pintype "passive"))
      (node (ref "J11") (pin "1") (pinfunction "1_1") (pintype "passive"))
      (node (ref "R23") (pin "1") (pinfunction "1_1") (pintype "passive"))
      (node (ref "U1") (pin "4") (pinfunction "RTC_GPIO4,TOUCH4,ADC1_CH3_4") (pintype "passive"))
    )
    (net (code "30") (name "/补水电磁阀") (class "Default")
      (node (ref "R38") (pin "2") (pinfunction "2_2") (pintype "passive"))
      (node (ref "U1") (pin "38") (pinfunction "RTC_GPIO2,TOUCH2,ADC1_CH1_38") (pintype "passive"))
    )
    (net (code "31") (name "/输出压力") (class "Default")
      (node (ref "C28") (pin "1") (pinfunction "1_1") (pintype "passive"))
      (node (ref "C29") (pin "1") (pinfunction "1_1") (pintype "passive"))
      (node (ref "D4") (pin "K") (pintype "passive"))
      (node (ref "R20") (pin "1") (pinfunction "1_1") (pintype "passive"))
      (node (ref "R21") (pin "1") (pinfunction "1_1") (pintype "passive"))
      (node (ref "U1") (pin "8") (pinfunction "RTC_GPIO15,U0RTS,ADC2_CH4,XTAL_32K_P_8") (pintype "passive"))
    )
    (net (code "32") (name "/过滤使用时间清零") (class "Default")
      (node (ref "C23") (pin "1") (pinfunction "1_1") (pintype "passive"))
      (node (ref "R18") (pin "2") (pinfunction "2_2") (pintype "passive"))
      (node (ref "U1") (pin "18") (pinfunction "RTC_GPIO10,TOUCH10,ADC1_CH9,FSPICS0_18") (pintype "passive"))
      (node (ref "key4") (pin "3") (pinfunction "3_3") (pintype "passive"))
      (node (ref "key4") (pin "4") (pinfunction "4_4") (pintype "passive"))
    )
    (net (code "33") (name "DGND") (class "Default")
      (node (ref "C12") (pin "1") (pinfunction "1_1") (pintype "passive"))
      (node (ref "C13") (pin "1") (pinfunction "1_1") (pintype "passive"))
      (node (ref "C15") (pin "1") (pinfunction "1_1") (pintype "passive"))
      (node (ref "C2") (pin "2") (pinfunction "2_2") (pintype "passive"))
      (node (ref "C5") (pin "2") (pinfunction "2_2") (pintype "passive"))
      (node (ref "C6") (pin "2") (pinfunction "2_2") (pintype "passive"))
      (node (ref "DT4") (pin "A") (pinfunction "A_A") (pintype "passive"))
      (node (ref "EC5") (pin "2") (pinfunction "E_2") (pintype "passive"))
      (node (ref "IC1") (pin "4") (pinfunction "GND_4") (pintype "passive"))
      (node (ref "IC2") (pin "4") (pinfunction "GND1_4") (pintype "passive"))
      (node (ref "J1") (pin "2") (pinfunction "2_2") (pintype "passive"))
      (node (ref "J4") (pin "1") (pinfunction "1_1") (pintype "passive"))
      (node (ref "R1") (pin "1") (pinfunction "1_1") (pintype "passive"))
      (node (ref "R15") (pin "2") (pinfunction "2_2") (pintype "passive"))
      (node (ref "R2") (pin "1") (pinfunction "1_1") (pintype "passive"))
      (node (ref "R8") (pin "2") (pinfunction "2_2") (pintype "passive"))
      (node (ref "R9") (pin "2") (pinfunction "2_2") (pintype "passive"))
      (node (ref "S1") (pin "3") (pinfunction "ISO_GND_3") (pintype "passive"))
    )
    (net (code "34") (name "GND") (class "Default")
      (node (ref "B1") (pin "4") (pinfunction "-_4") (pintype "passive"))
      (node (ref "BAT1") (pin "2") (pinfunction "-_2") (pintype "passive"))
      (node (ref "C10") (pin "2") (pinfunction "2_2") (pintype "passive"))
      (node (ref "C11") (pin "2") (pinfunction "2_2") (pintype "passive"))
      (node (ref "C14") (pin "1") (pinfunction "1_1") (pintype "passive"))
      (node (ref "C16") (pin "1") (pinfunction "1_1") (pintype "passive"))
      (node (ref "C18") (pin "2") (pinfunction "2_2") (pintype "passive"))
      (node (ref "C19") (pin "2") (pinfunction "2_2") (pintype "passive"))
      (node (ref "C20") (pin "1") (pinfunction "1_1") (pintype "passive"))
      (node (ref "C23") (pin "2") (pinfunction "2_2") (pintype "passive"))
      (node (ref "C24") (pin "2") (pinfunction "2_2") (pintype "passive"))
      (node (ref "C25") (pin "2") (pinfunction "2_2") (pintype "passive"))
      (node (ref "C26") (pin "1") (pinfunction "1_1") (pintype "passive"))
      (node (ref "C27") (pin "1") (pinfunction "1_1") (pintype "passive"))
      (node (ref "C28") (pin "2") (pinfunction "2_2") (pintype "passive"))
      (node (ref "C29") (pin "2") (pinfunction "2_2") (pintype "passive"))
      (node (ref "C30") (pin "2") (pinfunction "2_2") (pintype "passive"))
      (node (ref "C31") (pin "2") (pinfunction "2_2") (pintype "passive"))
      (node (ref "C32") (pin "1") (pinfunction "1_1") (pintype "passive"))
      (node (ref "C33") (pin "2") (pinfunction "2_2") (pintype "passive"))
      (node (ref "C34") (pin "2") (pinfunction "2_2") (pintype "passive"))
      (node (ref "C36") (pin "2") (pinfunction "2_2") (pintype "passive"))
      (node (ref "C37") (pin "2") (pinfunction "2_2") (pintype "passive"))
      (node (ref "C38") (pin "2") (pinfunction "2_2") (pintype "passive"))
      (node (ref "C39") (pin "2") (pinfunction "2_2") (pintype "passive"))
      (node (ref "C40") (pin "2") (pinfunction "2_2") (pintype "passive"))
      (node (ref "C41") (pin "2") (pinfunction "2_2") (pintype "passive"))
      (node (ref "C42") (pin "2") (pinfunction "2_2") (pintype "passive"))
      (node (ref "C43") (pin "2") (pinfunction "2_2") (pintype "passive"))
      (node (ref "C44") (pin "2") (pinfunction "2_2") (pintype "passive"))
      (node (ref "C45") (pin "1") (pinfunction "1_1") (pintype "passive"))
      (node (ref "C46") (pin "1") (pinfunction "1_1") (pintype "passive"))
      (node (ref "C47") (pin "2") (pinfunction "2_2") (pintype "passive"))
      (node (ref "C48") (pin "2") (pinfunction "2_2") (pintype "passive"))
      (node (ref "C49") (pin "2") (pinfunction "2_2") (pintype "passive"))
      (node (ref "C50") (pin "2") (pinfunction "2_2") (pintype "passive"))
      (node (ref "C51") (pin "2") (pinfunction "2_2") (pintype "passive"))
      (node (ref "C52") (pin "2") (pinfunction "2_2") (pintype "passive"))
      (node (ref "C7") (pin "1") (pinfunction "1_1") (pintype "passive"))
      (node (ref "C8") (pin "1") (pinfunction "1_1") (pintype "passive"))
      (node (ref "C9") (pin "2") (pinfunction "2_2") (pintype "passive"))
      (node (ref "D10") (pin "A") (pintype "passive"))
      (node (ref "D13") (pin "A") (pintype "passive"))
      (node (ref "D14") (pin "A") (pintype "passive"))
      (node (ref "D16") (pin "A") (pintype "passive"))
      (node (ref "D17") (pin "A") (pintype "passive"))
      (node (ref "D18") (pin "A") (pintype "passive"))
      (node (ref "D2") (pin "A") (pintype "passive"))
      (node (ref "D4") (pin "A") (pintype "passive"))
      (node (ref "D6") (pin "A") (pintype "passive"))
      (node (ref "D7") (pin "A") (pinfunction "A_A") (pintype "passive"))
      (node (ref "D8") (pin "A") (pintype "passive"))
      (node (ref "DT1") (pin "2") (pinfunction "2_2") (pintype "passive"))
      (node (ref "DT3") (pin "2") (pinfunction "2_2") (pintype "passive"))
      (node (ref "EC1") (pin "2") (pinfunction "E_2") (pintype "passive"))
      (node (ref "EC2") (pin "2") (pinfunction "E_2") (pintype "passive"))
      (node (ref "EC3") (pin "2") (pinfunction "E_2") (pintype "passive"))
      (node (ref "EC4") (pin "2") (pinfunction "E_2") (pintype "passive"))
      (node (ref "IC2") (pin "5") (pinfunction "GND2_5") (pintype "passive"))
      (node (ref "IC3") (pin "1") (pinfunction "GND_1") (pintype "passive"))
      (node (ref "IC4") (pin "4") (pinfunction "GND_4") (pintype "passive"))
      (node (ref "IC5") (pin "2") (pinfunction "GND_2") (pintype "passive"))
      (node (ref "IC5") (pin "4") (pinfunction "VIN-_4") (pintype "passive"))
      (node (ref "IC6") (pin "5") (pinfunction "GND_5") (pintype "passive"))
      (node (ref "IC7") (pin "1") (pinfunction "GND//ADJ_1") (pintype "passive"))
      (node (ref "IC8") (pin "1") (pinfunction "GND//ADJ_1") (pintype "passive"))
      (node (ref "J10") (pin "1") (pinfunction "1_1") (pintype "passive"))
      (node (ref "J12") (pin "1") (pinfunction "1_1") (pintype "passive"))
      (node (ref "J13") (pin "1") (pinfunction "1_1") (pintype "passive"))
      (node (ref "J15") (pin "4") (pinfunction "4_4") (pintype "passive"))
      (node (ref "J16") (pin "1") (pinfunction "1_1") (pintype "passive"))
      (node (ref "J19") (pin "2") (pinfunction "2_2") (pintype "passive"))
      (node (ref "J21") (pin "1") (pinfunction "1_1") (pintype "passive"))
      (node (ref "J3") (pin "1") (pinfunction "1_1") (pintype "passive"))
      (node (ref "J5") (pin "1") (pinfunction "1_1") (pintype "passive"))
      (node (ref "J6") (pin "1") (pinfunction "1_1") (pintype "passive"))
      (node (ref "J7") (pin "1") (pinfunction "1_1") (pintype "passive"))
      (node (ref "J8") (pin "1") (pinfunction "1_1") (pintype "passive"))
      (node (ref "J9") (pin "1") (pinfunction "1_1") (pintype "passive"))
      (node (ref "Q1") (pin "3") (pinfunction "E_3") (pintype "passive"))
      (node (ref "Q2") (pin "3") (pinfunction "E_3") (pintype "passive"))
      (node (ref "Q3") (pin "3") (pinfunction "E_3") (pintype "passive"))
      (node (ref "Q4") (pin "3") (pinfunction "E_3") (pintype "passive"))
      (node (ref "R17") (pin "1") (pinfunction "1_1") (pintype "passive"))
      (node (ref "R21") (pin "2") (pinfunction "2_2") (pintype "passive"))
      (node (ref "R23") (pin "2") (pinfunction "2_2") (pintype "passive"))
      (node (ref "R28") (pin "2") (pinfunction "2_2") (pintype "passive"))
      (node (ref "R29") (pin "1") (pinfunction "1_1") (pintype "passive"))
      (node (ref "R3") (pin "2") (pinfunction "2_2") (pintype "passive"))
      (node (ref "R30") (pin "2") (pinfunction "2_2") (pintype "passive"))
      (node (ref "R36") (pin "2") (pinfunction "2_2") (pintype "passive"))
      (node (ref "R39") (pin "2") (pinfunction "2_2") (pintype "passive"))
      (node (ref "R4") (pin "4") (pinfunction "4_4") (pintype "passive"))
      (node (ref "R41") (pin "2") (pinfunction "2_2") (pintype "passive"))
      (node (ref "R43") (pin "1") (pinfunction "1_1") (pintype "passive"))
      (node (ref "R44") (pin "2") (pinfunction "2_2") (pintype "passive"))
      (node (ref "R48") (pin "1") (pinfunction "1_1") (pintype "passive"))
      (node (ref "R49") (pin "2") (pinfunction "2_2") (pintype "passive"))
      (node (ref "R51") (pin "2") (pinfunction "2_2") (pintype "passive"))
      (node (ref "R52") (pin "2") (pinfunction "2_2") (pintype "passive"))
      (node (ref "S1") (pin "2") (pinfunction "GND_2") (pintype "passive"))
      (node (ref "S2") (pin "1") (pinfunction "GND_1") (pintype "passive"))
      (node (ref "S2") (pin "5") (pinfunction "GND_5") (pintype "passive"))
      (node (ref "U1") (pin "1") (pinfunction "GND_1") (pintype "passive"))
      (node (ref "U1") (pin "40") (pinfunction "接地_40") (pintype "passive"))
      (node (ref "U1") (pin "41") (pinfunction "接地_41") (pintype "passive"))
      (node (ref "key1") (pin "1") (pinfunction "1_1") (pintype "passive"))
      (node (ref "key1") (pin "2") (pinfunction "2_2") (pintype "passive"))
      (node (ref "key2") (pin "1") (pinfunction "1_1") (pintype "passive"))
      (node (ref "key2") (pin "2") (pinfunction "2_2") (pintype "passive"))
      (node (ref "key3") (pin "1") (pinfunction "1_1") (pintype "passive"))
      (node (ref "key3") (pin "2") (pinfunction "2_2") (pintype "passive"))
      (node (ref "key4") (pin "1") (pinfunction "1_1") (pintype "passive"))
      (node (ref "key4") (pin "2") (pinfunction "2_2") (pintype "passive"))
    )
    (net (code "35") (name "Net-(C35-Pad1)") (class "Default")
      (node (ref "C35") (pin "1") (pinfunction "1_1") (pintype "passive"))
      (node (ref "F2") (pin "1") (pinfunction "1_1") (pintype "passive"))
      (node (ref "J15") (pin "1") (pinfunction "1_1") (pintype "passive"))
    )
    (net (code "36") (name "Net-(C35-Pad2)") (class "Default")
      (node (ref "C35") (pin "2") (pinfunction "2_2") (pintype "passive"))
      (node (ref "F3") (pin "1") (pinfunction "1_1") (pintype "passive"))
      (node (ref "J15") (pin "2") (pinfunction "2_2") (pintype "passive"))
    )
    (net (code "37") (name "Net-(D3-PadK)") (class "Default")
      (node (ref "D3") (pin "K") (pinfunction "K_K") (pintype "passive"))
      (node (ref "R19") (pin "1") (pinfunction "1_1") (pintype "passive"))
    )
    (net (code "38") (name "Net-(D7-PadK)") (class "Default")
      (node (ref "D7") (pin "K") (pinfunction "K_K") (pintype "passive"))
      (node (ref "J12") (pin "2") (pinfunction "2_2") (pintype "passive"))
      (node (ref "R26") (pin "1") (pinfunction "1_1") (pintype "passive"))
    )
    (net (code "39") (name "Net-(D12-PadK)") (class "Default")
      (node (ref "D12") (pin "K") (pinfunction "K_K") (pintype "passive"))
      (node (ref "L3") (pin "1") (pinfunction "1_1") (pintype "passive"))
    )
    (net (code "40") (name "Net-(D_LED1-Pad1)") (class "Default")
      (node (ref "D_LED1") (pin "1") (pinfunction "1_1") (pintype "passive"))
      (node (ref "R4") (pin "2") (pinfunction "2_2") (pintype "passive"))
    )
    (net (code "41") (name "Net-(D_LED1-Pad4)") (class "Default")
      (node (ref "D_LED1") (pin "4") (pinfunction "4_4") (pintype "passive"))
      (node (ref "R4") (pin "1") (pinfunction "1_1") (pintype "passive"))
    )
    (net (code "42") (name "Net-(F1-Pad2)") (class "Default")
      (node (ref "F1") (pin "2") (pinfunction "2_2") (pintype "passive"))
      (node (ref "J1") (pin "1") (pinfunction "1_1") (pintype "passive"))
    )
    (net (code "43") (name "Net-(IC1-I_AN)") (class "Default")
      (node (ref "C6") (pin "1") (pinfunction "1_1") (pintype "passive"))
      (node (ref "IC1") (pin "2") (pinfunction "I_AN_2") (pintype "passive"))
      (node (ref "R9") (pin "1") (pinfunction "1_1") (pintype "passive"))
    )
    (net (code "44") (name "Net-(IC1-I_AP)") (class "Default")
      (node (ref "C5") (pin "1") (pinfunction "1_1") (pintype "passive"))
      (node (ref "IC1") (pin "1") (pinfunction "I_AP_1") (pintype "passive"))
      (node (ref "R6") (pin "1") (pinfunction "1_1") (pintype "passive"))
    )
    (net (code "45") (name "Net-(IC1-RX)") (class "Default")
      (node (ref "IC1") (pin "7") (pinfunction "RX_7") (pintype "passive"))
      (node (ref "IC2") (pin "2") (pinfunction "VOA_2") (pintype "passive"))
    )
    (net (code "46") (name "Net-(IC1-TX)") (class "Default")
      (node (ref "IC1") (pin "6") (pinfunction "TX_6") (pintype "passive"))
      (node (ref "IC2") (pin "3") (pinfunction "VIB_3") (pintype "passive"))
    )
    (net (code "47") (name "Net-(IC1-VP)") (class "Default")
      (node (ref "C13") (pin "2") (pinfunction "2_2") (pintype "passive"))
      (node (ref "DT4") (pin "K") (pinfunction "K_K") (pintype "passive"))
      (node (ref "IC1") (pin "3") (pinfunction "VP_3") (pintype "passive"))
      (node (ref "R14") (pin "2") (pinfunction "2_2") (pintype "passive"))
      (node (ref "R15") (pin "1") (pinfunction "1_1") (pintype "passive"))
    )
    (net (code "48") (name "Net-(IC1-VREF)") (class "Default")
      (node (ref "C12") (pin "2") (pinfunction "2_2") (pintype "passive"))
      (node (ref "IC1") (pin "5") (pinfunction "VREF_5") (pintype "passive"))
    )
    (net (code "49") (name "Net-(IC4-X1)") (class "Default")
      (node (ref "C25") (pin "1") (pinfunction "1_1") (pintype "passive"))
      (node (ref "IC4") (pin "1") (pinfunction "X1_1") (pintype "passive"))
      (node (ref "Y1") (pin "1") (pinfunction "OSC1_1") (pintype "passive"))
    )
    (net (code "50") (name "Net-(IC4-X2)") (class "Default")
      (node (ref "C24") (pin "1") (pinfunction "1_1") (pintype "passive"))
      (node (ref "IC4") (pin "2") (pinfunction "X2_2") (pintype "passive"))
      (node (ref "Y1") (pin "2") (pinfunction "OSC2_2") (pintype "passive"))
    )
    (net (code "51") (name "Net-(IC5-OUT)") (class "Default")
      (node (ref "IC5") (pin "5") (pinfunction "OUT_5") (pintype "passive"))
      (node (ref "R26") (pin "2") (pinfunction "2_2") (pintype "passive"))
    )
    (net (code "52") (name "Net-(IC6-A)") (class "Default")
      (node (ref "C32") (pin "2") (pinfunction "2_2") (pintype "passive"))
      (node (ref "DT1") (pin "1") (pinfunction "1_1") (pintype "passive"))
      (node (ref "DT2") (pin "1") (pinfunction "1_1") (pintype "passive"))
      (node (ref "F2") (pin "2") (pinfunction "2_2") (pintype "passive"))
      (node (ref "IC6") (pin "6") (pinfunction "A_6") (pintype "passive"))
      (node (ref "R29") (pin "2") (pinfunction "2_2") (pintype "passive"))
      (node (ref "R31") (pin "2") (pinfunction "2_2") (pintype "passive"))
    )
    (net (code "53") (name "Net-(IC6-B)") (class "Default")
      (node (ref "C38") (pin "1") (pinfunction "1_1") (pintype "passive"))
      (node (ref "DT2") (pin "2") (pinfunction "2_2") (pintype "passive"))
      (node (ref "DT3") (pin "1") (pinfunction "1_1") (pintype "passive"))
      (node (ref "F3") (pin "2") (pinfunction "2_2") (pintype "passive"))
      (node (ref "IC6") (pin "7") (pinfunction "B_7") (pintype "passive"))
      (node (ref "R31") (pin "1") (pinfunction "1_1") (pintype "passive"))
      (node (ref "R33") (pin "1") (pinfunction "1_1") (pintype "passive"))
    )
    (net (code "54") (name "Net-(IC7-VIN)") (class "Default")
      (node (ref "C45") (pin "2") (pinfunction "2_2") (pintype "passive"))
      (node (ref "C46") (pin "2") (pinfunction "2_2") (pintype "passive"))
      (node (ref "EC3") (pin "1") (pinfunction "1_1") (pintype "passive"))
      (node (ref "IC7") (pin "3") (pinfunction "VIN_3") (pintype "passive"))
      (node (ref "IC8") (pin "3") (pinfunction "VIN_3") (pintype "passive"))
      (node (ref "L3") (pin "2") (pinfunction "2_2") (pintype "passive"))
    )
    (net (code "55") (name "Net-(J4-Pad2)") (class "Default")
      (node (ref "J4") (pin "2") (pinfunction "2_2") (pintype "passive"))
      (node (ref "R5") (pin "1") (pinfunction "1_1") (pintype "passive"))
      (node (ref "R6") (pin "2") (pinfunction "2_2") (pintype "passive"))
      (node (ref "R8") (pin "1") (pinfunction "1_1") (pintype "passive"))
    )
    (net (code "56") (name "Net-(J10-Pad2)") (class "Default")
      (node (ref "J10") (pin "2") (pinfunction "2_2") (pintype "passive"))
      (node (ref "R20") (pin "2") (pinfunction "2_2") (pintype "passive"))
    )
    (net (code "57") (name "Net-(J16-Pad2)") (class "Default")
      (node (ref "J16") (pin "2") (pinfunction "2_2") (pintype "passive"))
      (node (ref "R34") (pin "2") (pinfunction "2_2") (pintype "passive"))
    )
    (net (code "58") (name "Net-(J17-Pad1)") (class "Default")
      (node (ref "J17") (pin "1") (pinfunction "1_1") (pintype "passive"))
      (node (ref "SPDT1") (pin "1") (pinfunction "1_1") (pintype "passive"))
    )
    (net (code "59") (name "Net-(J19-Pad3)") (class "Default")
      (node (ref "J19") (pin "3") (pinfunction "3_3") (pintype "passive"))
      (node (ref "R35") (pin "1") (pinfunction "1_1") (pintype "passive"))
    )
    (net (code "60") (name "Net-(J21-Pad2)") (class "Default")
      (node (ref "J21") (pin "2") (pinfunction "2_2") (pintype "passive"))
      (node (ref "R47") (pin "2") (pinfunction "2_2") (pintype "passive"))
    )
    (net (code "61") (name "Net-(J22-Pad1)") (class "Default")
      (node (ref "J22") (pin "1") (pinfunction "1_1") (pintype "passive"))
      (node (ref "SPDT2") (pin "1") (pinfunction "1_1") (pintype "passive"))
    )
    (net (code "62") (name "Net-(L1-N1-1)") (class "Default")
      (node (ref "C2") (pin "1") (pinfunction "1_1") (pintype "passive"))
      (node (ref "F1") (pin "1") (pinfunction "1_1") (pintype "passive"))
      (node (ref "L1") (pin "1") (pinfunction "N1-1_1") (pintype "passive"))
      (node (ref "R1") (pin "2") (pinfunction "2_2") (pintype "passive"))
    )
    (net (code "63") (name "Net-(L1-N2-1)") (class "Default")
      (node (ref "L1") (pin "3") (pinfunction "N2-1_3") (pintype "passive"))
      (node (ref "R2") (pin "2") (pinfunction "2_2") (pintype "passive"))
      (node (ref "R5") (pin "2") (pinfunction "2_2") (pintype "passive"))
    )
    (net (code "64") (name "Net-(Q1-B1)") (class "Default")
      (node (ref "Q1") (pin "1") (pinfunction "B1_1") (pintype "passive"))
      (node (ref "R27") (pin "1") (pinfunction "1_1") (pintype "passive"))
      (node (ref "R28") (pin "1") (pinfunction "1_1") (pintype "passive"))
    )
    (net (code "65") (name "Net-(Q1-C)") (class "Default")
      (node (ref "D5") (pin "A") (pinfunction "A_A") (pintype "passive"))
      (node (ref "Q1") (pin "2") (pinfunction "C_2") (pintype "passive"))
      (node (ref "R25") (pin "2") (pinfunction "2_2") (pintype "passive"))
      (node (ref "S3") (pin "2") (pinfunction "－_2") (pintype "passive"))
    )
    (net (code "66") (name "Net-(Q2-B1)") (class "Default")
      (node (ref "Q2") (pin "1") (pinfunction "B1_1") (pintype "passive"))
      (node (ref "R38") (pin "1") (pinfunction "1_1") (pintype "passive"))
      (node (ref "R39") (pin "1") (pinfunction "1_1") (pintype "passive"))
    )
    (net (code "67") (name "Net-(Q2-C)") (class "Default")
      (node (ref "D9") (pin "A") (pinfunction "A_A") (pintype "passive"))
      (node (ref "Q2") (pin "2") (pinfunction "C_2") (pintype "passive"))
      (node (ref "R32") (pin "1") (pinfunction "1_1") (pintype "passive"))
      (node (ref "SPDT1") (pin "3") (pinfunction "3_3") (pintype "passive"))
    )
    (net (code "68") (name "Net-(Q3-B1)") (class "Default")
      (node (ref "Q3") (pin "1") (pinfunction "B1_1") (pintype "passive"))
      (node (ref "R42") (pin "1") (pinfunction "1_1") (pintype "passive"))
      (node (ref "R44") (pin "1") (pinfunction "1_1") (pintype "passive"))
    )
    (net (code "69") (name "Net-(Q3-C)") (class "Default")
      (node (ref "D11") (pin "A") (pinfunction "A_A") (pintype "passive"))
      (node (ref "J18") (pin "1") (pinfunction "1_1") (pintype "passive"))
      (node (ref "Q3") (pin "2") (pinfunction "C_2") (pintype "passive"))
      (node (ref "R40") (pin "2") (pinfunction "2_2") (pintype "passive"))
    )
    (net (code "70") (name "Net-(Q4-B1)") (class "Default")
      (node (ref "Q4") (pin "1") (pinfunction "B1_1") (pintype "passive"))
      (node (ref "R46") (pin "1") (pinfunction "1_1") (pintype "passive"))
      (node (ref "R51") (pin "1") (pinfunction "1_1") (pintype "passive"))
    )
    (net (code "71") (name "Net-(Q4-C)") (class "Default")
      (node (ref "D15") (pin "A") (pinfunction "A_A") (pintype "passive"))
      (node (ref "Q4") (pin "2") (pinfunction "C_2") (pintype "passive"))
      (node (ref "R45") (pin "2") (pinfunction "2_2") (pintype "passive"))
      (node (ref "SPDT2") (pin "3") (pinfunction "3_3") (pintype "passive"))
    )
    (net (code "72") (name "Net-(R10-Pad2)") (class "Default")
      (node (ref "R10") (pin "2") (pinfunction "2_2") (pintype "passive"))
      (node (ref "R11") (pin "2") (pinfunction "2_2") (pintype "passive"))
    )
    (net (code "73") (name "Net-(R11-Pad1)") (class "Default")
      (node (ref "R11") (pin "1") (pinfunction "1_1") (pintype "passive"))
      (node (ref "R12") (pin "1") (pinfunction "1_1") (pintype "passive"))
    )
    (net (code "74") (name "Net-(R12-Pad2)") (class "Default")
      (node (ref "R12") (pin "2") (pinfunction "2_2") (pintype "passive"))
      (node (ref "R13") (pin "2") (pinfunction "2_2") (pintype "passive"))
    )
    (net (code "75") (name "Net-(R13-Pad1)") (class "Default")
      (node (ref "R13") (pin "1") (pinfunction "1_1") (pintype "passive"))
      (node (ref "R14") (pin "1") (pinfunction "1_1") (pintype "passive"))
    )
    (net (code "76") (name "VCC 12V") (class "Default")
      (node (ref "B1") (pin "3") (pinfunction "+_3") (pintype "passive"))
      (node (ref "C16") (pin "2") (pinfunction "2_2") (pintype "passive"))
      (node (ref "D11") (pin "K") (pinfunction "K_K") (pintype "passive"))
      (node (ref "D12") (pin "A") (pinfunction "A_A") (pintype "passive"))
      (node (ref "D15") (pin "K") (pinfunction "K_K") (pintype "passive"))
      (node (ref "D9") (pin "K") (pinfunction "K_K") (pintype "passive"))
      (node (ref "EC2") (pin "1") (pinfunction "1_1") (pintype "passive"))
      (node (ref "IC5") (pin "1") (pinfunction "VCC_1") (pintype "passive"))
      (node (ref "J12") (pin "3") (pinfunction "3_3") (pintype "passive"))
      (node (ref "J15") (pin "3") (pinfunction "3_3") (pintype "passive"))
      (node (ref "J18") (pin "2") (pinfunction "2_2") (pintype "passive"))
      (node (ref "R32") (pin "2") (pinfunction "2_2") (pintype "passive"))
      (node (ref "R40") (pin "1") (pinfunction "1_1") (pintype "passive"))
      (node (ref "R45") (pin "1") (pinfunction "1_1") (pintype "passive"))
      (node (ref "S1") (pin "1") (pinfunction "VIN_1") (pintype "passive"))
      (node (ref "S2") (pin "2") (pinfunction "VIN_2") (pintype "passive"))
      (node (ref "S2") (pin "3") (pinfunction "VIN_3") (pintype "passive"))
      (node (ref "SPDT1") (pin "4") (pinfunction "4_4") (pintype "passive"))
      (node (ref "SPDT2") (pin "4") (pinfunction "4_4") (pintype "passive"))
    )
    (net (code "77") (name "VCC3.0V") (class "Default")
      (node (ref "C47") (pin "1") (pinfunction "1_1") (pintype "passive"))
      (node (ref "C48") (pin "1") (pinfunction "1_1") (pintype "passive"))
      (node (ref "D16") (pin "K") (pintype "passive"))
      (node (ref "IC8") (pin "2") (pinfunction "VOUT_2") (pintype "passive"))
      (node (ref "J11") (pin "2") (pinfunction "2_2") (pintype "passive"))
      (node (ref "J14") (pin "2") (pinfunction "2_2") (pintype "passive"))
      (node (ref "J20") (pin "2") (pinfunction "2_2") (pintype "passive"))
      (node (ref "J23") (pin "2") (pinfunction "2_2") (pintype "passive"))
      (node (ref "R48") (pin "2") (pinfunction "2_2") (pintype "passive"))
    )
    (net (code "78") (name "VCC3.3V") (class "Default")
      (node (ref "C10") (pin "1") (pinfunction "1_1") (pintype "passive"))
      (node (ref "C19") (pin "1") (pinfunction "1_1") (pintype "passive"))
      (node (ref "C20") (pin "2") (pinfunction "2_2") (pintype "passive"))
      (node (ref "C7") (pin "2") (pinfunction "2_2") (pintype "passive"))
      (node (ref "C8") (pin "2") (pinfunction "2_2") (pintype "passive"))
      (node (ref "C9") (pin "1") (pinfunction "1_1") (pintype "passive"))
      (node (ref "D2") (pin "K") (pintype "passive"))
      (node (ref "D3") (pin "A") (pinfunction "A_A") (pintype "passive"))
      (node (ref "D_LED1") (pin "2") (pinfunction "2_2") (pintype "passive"))
      (node (ref "D_LED1") (pin "3") (pinfunction "3_3") (pintype "passive"))
      (node (ref "EC4") (pin "1") (pinfunction "1_1") (pintype "passive"))
      (node (ref "IC2") (pin "8") (pinfunction "VCC2_8") (pintype "passive"))
      (node (ref "IC3") (pin "2") (pinfunction "VOUT_2") (pintype "passive"))
      (node (ref "R16") (pin "1") (pinfunction "1_1") (pintype "passive"))
      (node (ref "R17") (pin "2") (pinfunction "2_2") (pintype "passive"))
      (node (ref "R18") (pin "1") (pinfunction "1_1") (pintype "passive"))
      (node (ref "R24") (pin "3") (pinfunction "3_3") (pintype "passive"))
      (node (ref "R24") (pin "4") (pinfunction "4_4") (pintype "passive"))
      (node (ref "R53") (pin "2") (pinfunction "2_2") (pintype "passive"))
      (node (ref "R7") (pin "2") (pinfunction "2_2") (pintype "passive"))
      (node (ref "U1") (pin "2") (pinfunction "3.3V_2") (pintype "passive"))
    )
    (net (code "79") (name "VCC3.3V_P") (class "Default")
      (node (ref "C15") (pin "2") (pinfunction "2_2") (pintype "passive"))
      (node (ref "EC5") (pin "1") (pinfunction "1_1") (pintype "passive"))
      (node (ref "IC1") (pin "8") (pinfunction "VDD_8") (pintype "passive"))
      (node (ref "IC2") (pin "1") (pinfunction "VCC1_1") (pintype "passive"))
      (node (ref "S1") (pin "4") (pinfunction "+Vout_4") (pintype "passive"))
    )
    (net (code "80") (name "VCC5.0V") (class "Default")
      (node (ref "C26") (pin "2") (pinfunction "2_2") (pintype "passive"))
      (node (ref "C27") (pin "2") (pinfunction "2_2") (pintype "passive"))
      (node (ref "C43") (pin "1") (pinfunction "1_1") (pintype "passive"))
      (node (ref "C44") (pin "1") (pinfunction "1_1") (pintype "passive"))
      (node (ref "D14") (pin "K") (pintype "passive"))
      (node (ref "IC4") (pin "8") (pinfunction "Vcc(必须5V)_8") (pintype "passive"))
      (node (ref "IC7") (pin "2") (pinfunction "VOUT_2") (pintype "passive"))
      (node (ref "J10") (pin "3") (pinfunction "3_3") (pintype "passive"))
      (node (ref "J16") (pin "3") (pinfunction "3_3") (pintype "passive"))
      (node (ref "J21") (pin "3") (pinfunction "3_3") (pintype "passive"))
      (node (ref "R43") (pin "2") (pinfunction "2_2") (pintype "passive"))
    )
    (net (code "81") (name "VCC5V") (class "Default")
      (node (ref "C14") (pin "2") (pinfunction "2_2") (pintype "passive"))
      (node (ref "C36") (pin "1") (pinfunction "1_1") (pintype "passive"))
      (node (ref "C37") (pin "1") (pinfunction "1_1") (pintype "passive"))
      (node (ref "D5") (pin "K") (pinfunction "K_K") (pintype "passive"))
      (node (ref "EC1") (pin "1") (pinfunction "1_1") (pintype "passive"))
      (node (ref "IC3") (pin "3") (pinfunction "VIN_3") (pintype "passive"))
      (node (ref "IC6") (pin "8") (pinfunction "VCC_8") (pintype "passive"))
      (node (ref "J13") (pin "4") (pinfunction "4_4") (pintype "passive"))
      (node (ref "R25") (pin "1") (pinfunction "1_1") (pintype "passive"))
      (node (ref "R33") (pin "2") (pinfunction "2_2") (pintype "passive"))
      (node (ref "S2") (pin "4") (pinfunction "OUT_4") (pintype "passive"))
      (node (ref "S3") (pin "1") (pinfunction "+_1") (pintype "passive"))
    )
    (net (code "82") (name "unconnected-(IC4-SQW_脉冲输出-Pad7)") (class "Default")
      (node (ref "IC4") (pin "7") (pinfunction "SQW_脉冲输出_7") (pintype "passive"))
    )
    (net (code "83") (name "unconnected-(U1-GPIO45-Pad26)") (class "Default")
      (node (ref "U1") (pin "26") (pinfunction "GPIO45_26") (pintype "passive"))
    )
    (net (code "84") (name "unconnected-(U1-GPIO46-Pad16)") (class "Default")
      (node (ref "U1") (pin "16") (pinfunction "GPIO46_16") (pintype "passive"))
    )
    (net (code "85") (name "unconnected-(U1-RTC_GPIO3,TOUCH3,ADC1_CH2-Pad15)") (class "Default")
      (node (ref "U1") (pin "15") (pinfunction "RTC_GPIO3,TOUCH3,ADC1_CH2_15") (pintype "passive"))
    )
    (net (code "86") (name "unconnected-(U1-RTC_GPIO11,TOUCH11,ADC2_CH0-Pad19)") (class "Default")
      (node (ref "U1") (pin "19") (pinfunction "RTC_GPIO11,TOUCH11,ADC2_CH0_19") (pintype "passive"))
    )
    (net (code "87") (name "unconnected-(U1-RTC_GPIO12,TOUCH12,ADC2_CH1-Pad20)") (class "Default")
      (node (ref "U1") (pin "20") (pinfunction "RTC_GPIO12,TOUCH12,ADC2_CH1_20") (pintype "passive"))
    )
    (net (code "88") (name "unconnected-(U1-SPIDQS,GPIO37,FSPIQ(不可用)-Pad30)") (class "Default")
      (node (ref "U1") (pin "30") (pinfunction "SPIDQS,GPIO37,FSPIQ(不可用)_30") (pintype "passive"))
    )
    (net (code "89") (name "unconnected-(U1-SPIIO6,GPIO35,FSPID(不可用)-Pad28)") (class "Default")
      (node (ref "U1") (pin "28") (pinfunction "SPIIO6,GPIO35,FSPID(不可用)_28") (pintype "passive"))
    )
    (net (code "90") (name "unconnected-(U1-SPIIO7,GPIO36,FSPICLK(不可用)-Pad29)") (class "Default")
      (node (ref "U1") (pin "29") (pinfunction "SPIIO7,GPIO36,FSPICLK(不可用)_29") (pintype "passive"))
    )
    (net (code "91") (name "地") (class "Default")
      (node (ref "C1") (pin "1") (pinfunction "1_1") (pintype "passive"))
      (node (ref "C4") (pin "2") (pinfunction "2_2") (pintype "passive"))
      (node (ref "J1") (pin "3") (pinfunction "3_3") (pintype "passive"))
      (node (ref "J2") (pin "3") (pinfunction "3_3") (pintype "passive"))
      (node (ref "R3") (pin "1") (pinfunction "1_1") (pintype "passive"))
    )
  )
)
